# MCU_SLAVE.net
KiCad netlist of a schematic drawn in Altium Designer
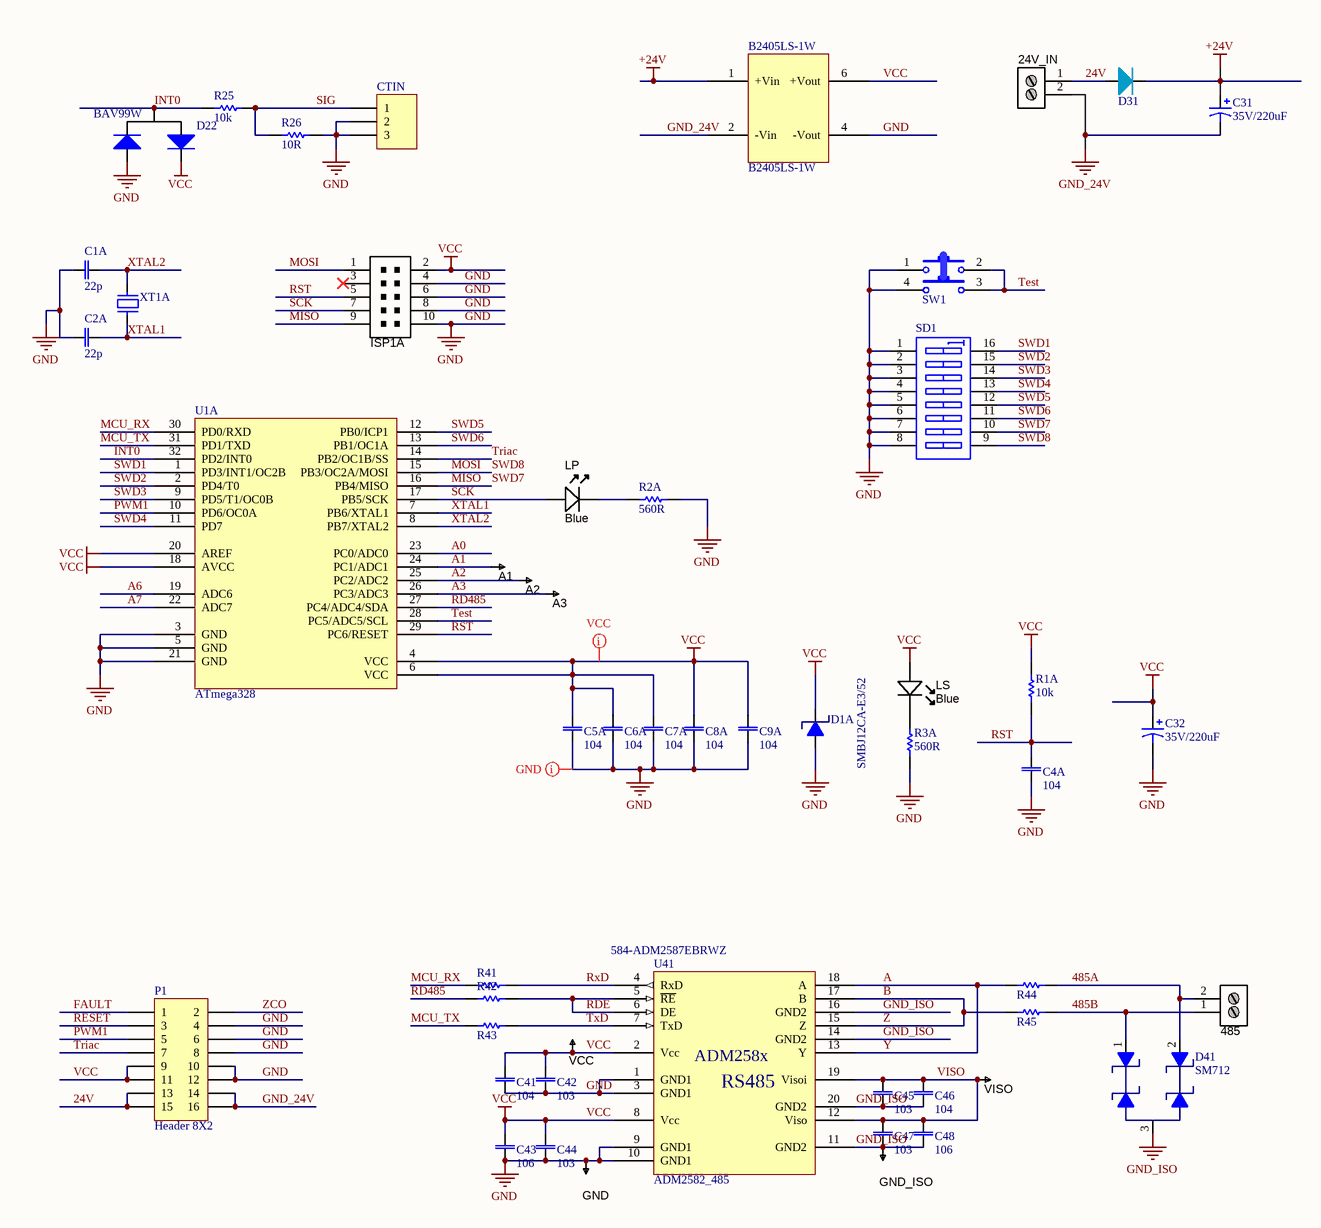
[diagram p0: MCU_SLAVE.SchDoc]

(export (version "E")
  (design (tool "Eeschema 10.0.6"))
  (components
    (comp (ref "24V_IN")
      (value "Giắc xanh 5.08mm")
      (footprint "2P_PCB1")
      (description "Terminal Block Screw Type THT 2-Position 3.81mm pitch")
      (libsource (lib "PBL - Connectors") (part "2P_ScrewTerm_90S_3.81MM"))
    )
    (comp (ref "485")
      (value "Giắc xanh 5.08mm")
      (footprint "2P_PCB1")
      (description "Terminal Block Screw Type THT 2-Position 3.81mm pitch")
      (libsource (lib "") (part "2P_ScrewTerm_90S_3.81MM_1"))
    )
    (comp (ref "A1")
      (value "TESTPOINT")
      (footprint "TP-R60")
      (description "SMD test pin")
      (libsource (lib "PBL - Test Points") (part "TESTPOINT"))
    )
    (comp (ref "A2")
      (value "TESTPOINT")
      (footprint "TP-R60")
      (description "SMD test pin")
      (libsource (lib "PBL - Test Points") (part "TESTPOINT"))
    )
    (comp (ref "A3")
      (value "TESTPOINT")
      (footprint "TP-R60")
      (description "SMD test pin")
      (libsource (lib "PBL - Test Points") (part "TESTPOINT"))
    )
    (comp (ref "B2405LS-1W")
      (value "B2405LS-1W")
      (footprint "Mornsun 1W")
      (libsource (lib "Tuan") (part "Mornsun 0505 1W"))
    )
    (comp (ref "C1A")
      (value "22p")
      (footprint "PBL - SMD Packages:CAPC2012N_F")
      (description "Capacitor non polarized")
      (fields (field (name "Comment") "Tụ điện dán 060322p"))
      (libsource (lib "Tuan") (part "CAP NP"))
    )
    (comp (ref "C2A")
      (value "22p")
      (footprint "PBL - SMD Packages:CAPC2012N_F")
      (description "Capacitor non polarized")
      (fields (field (name "Comment") "Tụ điện dán 060322p"))
      (libsource (lib "Tuan") (part "CAP NP"))
    )
    (comp (ref "C4A")
      (value "104")
      (footprint "PBL - SMD Packages:CAPC2012N_F")
      (description "Capacitor non polarized")
      (fields (field (name "Comment") "Tụ điện dán 0603104"))
      (libsource (lib "Tuan") (part "CAP NP"))
    )
    (comp (ref "C5A")
      (value "104")
      (footprint "PBL - SMD Packages:CAPC2012N_F")
      (description "Capacitor non polarized")
      (fields (field (name "Comment") "Tụ điện dán 0805104"))
      (libsource (lib "Tuan") (part "CAP NP"))
    )
    (comp (ref "C6A")
      (value "104")
      (footprint "PBL - SMD Packages:CAPC2012N_F")
      (description "Capacitor non polarized")
      (fields (field (name "Comment") "Tụ điện dán 0805104"))
      (libsource (lib "Tuan") (part "CAP NP"))
    )
    (comp (ref "C7A")
      (value "104")
      (footprint "PBL - SMD Packages:CAPC2012N_F")
      (description "Capacitor non polarized")
      (fields (field (name "Comment") "Tụ điện dán 0603104"))
      (libsource (lib "Tuan") (part "CAP NP"))
    )
    (comp (ref "C8A")
      (value "104")
      (footprint "PBL - SMD Packages:CAPC2012N_F")
      (description "Capacitor non polarized")
      (fields (field (name "Comment") "Tụ điện dán 0603104"))
      (libsource (lib "Tuan") (part "CAP NP"))
    )
    (comp (ref "C9A")
      (value "104")
      (footprint "PBL - SMD Packages:CAPC2012N_F")
      (description "Capacitor non polarized")
      (fields (field (name "Comment") "Tụ điện dán 0603104"))
      (libsource (lib "Tuan") (part "CAP NP"))
    )
    (comp (ref "C31")
      (value "35V/220uF")
      (footprint "CAPE3.5-5.0MM_Rad_10x14mm")
      (fields (field (name "Comment") "Tụ nhôm cắm35V/220uF"))
      (libsource (lib "Tuan") (part "Cap"))
    )
    (comp (ref "C32")
      (value "35V/220uF")
      (footprint "CAPE3.5-5.0MM_Rad_10x14mm")
      (fields (field (name "Comment") "Tụ nhôm cắm35V/220uF"))
      (libsource (lib "Tuan") (part "Cap"))
    )
    (comp (ref "C41")
      (value "104")
      (footprint "PBL - SMD Packages:CAPC2012N_F")
      (description "Capacitor non polarized")
      (fields (field (name "Comment") "Tụ điện dán 0805104"))
      (libsource (lib "Tuan") (part "CAP NP"))
    )
    (comp (ref "C42")
      (value "103")
      (footprint "PBL - SMD Packages:CAPC2012N_F")
      (description "Capacitor non polarized")
      (fields (field (name "Comment") "Tụ điện dán 0805103"))
      (libsource (lib "Tuan") (part "CAP NP"))
    )
    (comp (ref "C43")
      (value "106")
      (footprint "PBL - SMD Packages:CAPC2012N_F")
      (description "Capacitor non polarized")
      (fields (field (name "Comment") "Tụ điện dán 0805106"))
      (libsource (lib "Tuan") (part "CAP NP"))
    )
    (comp (ref "C44")
      (value "103")
      (footprint "PBL - SMD Packages:CAPC2012N_F")
      (description "Capacitor non polarized")
      (fields (field (name "Comment") "Tụ điện dán 0805103"))
      (libsource (lib "Tuan") (part "CAP NP"))
    )
    (comp (ref "C45")
      (value "103")
      (footprint "PBL - SMD Packages:CAPC2012N_F")
      (description "Capacitor non polarized")
      (fields (field (name "Comment") "Tụ điện dán 0805103"))
      (libsource (lib "Tuan") (part "CAP NP"))
    )
    (comp (ref "C46")
      (value "104")
      (footprint "PBL - SMD Packages:CAPC2012N_F")
      (description "Capacitor non polarized")
      (fields (field (name "Comment") "Tụ điện dán 0805104"))
      (libsource (lib "Tuan") (part "CAP NP"))
    )
    (comp (ref "C47")
      (value "103")
      (footprint "PBL - SMD Packages:CAPC2012N_F")
      (description "Capacitor non polarized")
      (fields (field (name "Comment") "Tụ điện dán 0805103"))
      (libsource (lib "Tuan") (part "CAP NP"))
    )
    (comp (ref "C48")
      (value "106")
      (footprint "PBL - SMD Packages:CAPC2012N_F")
      (description "Capacitor non polarized")
      (fields (field (name "Comment") "Tụ điện dán 0805106"))
      (libsource (lib "Tuan") (part "CAP NP"))
    )
    (comp (ref "CTIN")
      (value "Header 3")
      (footprint "HDR1X3")
      (description "Header, 3-Pin")
      (fields (field (name "PUBLISHER") "Altium Limited"))
      (libsource (lib "Miscellaneous Connectors") (part "Header 3"))
    )
    (comp (ref "D1A")
      (value "Đi ốt dánSMBJ12CA-E3/52")
      (footprint "DO-214AC")
      (description "TVS Diodes - Transient Voltage Suppressors")
      (fields (field (name "VL2") "SMBJ12CA-E3/52"))
      (libsource (lib "Tuan") (part "TVS Diodes"))
    )
    (comp (ref "D22")
      (value "Đi ốt dánBAV99Wchân SOT-323")
      (footprint "SOT323")
      (description "Diode Array 1 Pair Series Connection Standard 70V 215mA (DC) Surface Mount SC-70, SOT-323")
      (fields (field (name "VL1") "BAV99W"))
      (libsource (lib "Tuan") (part "BAV99W"))
    )
    (comp (ref "D31")
      (value "Đi ốt cắm")
      (footprint "PBL - SMD Packages:DO-214AC")
      (libsource (lib "Tuan") (part "Diode"))
    )
    (comp (ref "D41") (value "SM712") (footprint "SOT23 TOP") (libsource (lib "Tuan") (part "SM712")))
    (comp (ref "GND")
      (value "TESTPOINT")
      (footprint "TP-R60")
      (description "SMD test pin")
      (libsource (lib "PBL - Test Points") (part "TESTPOINT"))
    )
    (comp (ref "GND_ISO")
      (value "TESTPOINT")
      (footprint "TP-R60")
      (description "SMD test pin")
      (libsource (lib "PBL - Test Points") (part "TESTPOINT"))
    )
    (comp (ref "ISP1A")
      (value "Giắc đôi 5x2 chân 2.54mm")
      (footprint "10P_PCB_HEADER_BRD_MNT")
      (description "Header THD 10 POS Double-row 2.54mm pitch")
      (libsource (lib "PBL - Connectors") (part "CONN_HEADER_2x5P_0.100in_Male"))
    )
    (comp (ref "LP")
      (value "Blue")
      (footprint "LED-0805-K")
      (description "LED 0805 SMD Blue 100mcd 470nm")
      (fields (field (name "COLOR") "Blue"))
      (libsource (lib "PBL - Light Sources") (part "LED_SMD_Blue_0805_100mcd"))
    )
    (comp (ref "LS")
      (value "Blue")
      (footprint "LED-0805-K")
      (description "LED 0805 SMD Blue 100mcd 470nm")
      (fields (field (name "COLOR") "Blue"))
      (libsource (lib "PBL - Light Sources") (part "LED_SMD_Blue_0805_100mcd"))
    )
    (comp (ref "P1")
      (value "Header 8X2")
      (footprint "HDR2X8")
      (description "Header, 8-Pin, Dual row")
      (fields (field (name "PUBLISHER") "Altium Limited"))
      (libsource (lib "Miscellaneous Connectors") (part "Header 8X2"))
    )
    (comp (ref "R1A")
      (value "10k")
      (footprint "PBL - SMD Packages:RESC2012N_F")
      (description "Resistor")
      (fields (field (name "Comment") "Điện trở dán 060310k"))
      (libsource (lib "Tuan") (part "Res"))
    )
    (comp (ref "R2A")
      (value "560R")
      (footprint "PBL - SMD Packages:RESC2012N_F")
      (description "Resistor")
      (fields (field (name "Comment") "Điện trở dán 0603560R"))
      (libsource (lib "Tuan") (part "Res"))
    )
    (comp (ref "R3A")
      (value "560R")
      (footprint "PBL - SMD Packages:RESC2012N_F")
      (description "Resistor")
      (fields (field (name "Comment") "Điện trở dán 0603560R"))
      (libsource (lib "Tuan") (part "Res"))
    )
    (comp (ref "R25")
      (value "10k")
      (footprint "PBL - SMD Packages:RESC3216N")
      (description "Resistor")
      (fields (field (name "Comment") "Điện trở dán 120610k"))
      (libsource (lib "Tuan") (part "Res"))
    )
    (comp (ref "R26")
      (value "10R")
      (footprint "PBL - SMD Packages:RESC3216N")
      (description "Resistor")
      (fields (field (name "Comment") "Điện trở dán 120610R"))
      (libsource (lib "Tuan") (part "Res"))
    )
    (comp (ref "R41")
      (value "Điện trở dán 08050R")
      (footprint "PBL - SMD Packages:RESC2012N_F")
      (description "Resistor")
      (libsource (lib "Tuan") (part "Res"))
    )
    (comp (ref "R42")
      (value "Điện trở dán 08050R")
      (footprint "PBL - SMD Packages:RESC2012N_F")
      (description "Resistor")
      (libsource (lib "Tuan") (part "Res"))
    )
    (comp (ref "R43")
      (value "Điện trở dán 08050R")
      (footprint "PBL - SMD Packages:RESC2012N_F")
      (description "Resistor")
      (libsource (lib "Tuan") (part "Res"))
    )
    (comp (ref "R44")
      (value "Điện trở dán 08050R")
      (footprint "PBL - SMD Packages:RESC2012N_F")
      (description "Resistor")
      (libsource (lib "Tuan") (part "Res"))
    )
    (comp (ref "R45")
      (value "Điện trở dán 08050R")
      (footprint "PBL - SMD Packages:RESC2012N_F")
      (description "Resistor")
      (libsource (lib "Tuan") (part "Res"))
    )
    (comp (ref "SD1")
      (value "Công tắc gạt 8 kênh, 16 chân cắm DIP16")
      (footprint "DIP16/W0.3K")
      (description "DIP Switch, 8 Position, SPST")
      (libsource (lib "heromap") (part "SWDIP-8"))
    )
    (comp (ref "SW1")
      (value "Nút bấm 4 chân cắm12x12x6mm")
      (footprint "SW")
      (libsource (lib "Tuan") (part "SW-4P-Small"))
    )
    (comp (ref "U1A")
      (value "ATmega328")
      (footprint "TQFP32")
      (description "AVR AVR® ATmega Microcontroller IC 8-Bit 20MHz 8KB (4K x 16) FLASH 32-TQFP (7x7)")
      (libsource (lib "Tuan") (part "ATmega48/168/328"))
    )
    (comp (ref "U41")
      (value "ADM2582_485")
      (footprint "syhaunguyen:SO-20B")
      (description "ANALOG DEVICES   ADM2587EBRWZ   RS485 Transceiver, 3V-5.5V Supply, SOIC-20")
      (fields
        (field (name "SUPPLIER PART NUMBER 1") "584-ADM2587EBRWZ")
        (field (name "MANUFACTURER") "Analog Devices")
        (field (name "MANUFACTURER PART NUMBER") "ADM2587EBRWZ")
      )
      (libsource (lib "Tuan") (part "ADM2582_485"))
    )
    (comp (ref "VCC")
      (value "TESTPOINT")
      (footprint "TP-R60")
      (description "SMD test pin")
      (libsource (lib "PBL - Test Points") (part "TESTPOINT"))
    )
    (comp (ref "VISO")
      (value "TESTPOINT")
      (footprint "TP-R60")
      (description "SMD test pin")
      (libsource (lib "PBL - Test Points") (part "TESTPOINT"))
    )
    (comp (ref "XT1A")
      (value "Thạch anh cắm 16MHz")
      (footprint "XT2")
      (libsource (lib "Tuan") (part "Crystal"))
    )
  )
  (nets
    (net (code "1") (name "+24V") (class "Default")
      (node (ref "B2405LS-1W") (pin "1") (pinfunction "+Vin_1") (pintype "passive"))
      (node (ref "C31") (pin "1") (pinfunction "1_1") (pintype "passive"))
      (node (ref "D31") (pin "K") (pinfunction "K_K") (pintype "passive"))
    )
    (net (code "2") (name "/24V") (class "Default")
      (node (ref "24V_IN") (pin "1") (pinfunction "1_1") (pintype "passive"))
      (node (ref "D31") (pin "A") (pinfunction "A_A") (pintype "passive"))
      (node (ref "P1") (pin "13") (pinfunction "13_13") (pintype "passive"))
      (node (ref "P1") (pin "15") (pinfunction "15_15") (pintype "passive"))
    )
    (net (code "3") (name "/485A") (class "Default")
      (node (ref "485") (pin "2") (pinfunction "2_2") (pintype "passive"))
      (node (ref "D41") (pin "2") (pinfunction "IO2_2") (pintype "passive"))
      (node (ref "R44") (pin "2") (pinfunction "2_2") (pintype "passive"))
    )
    (net (code "4") (name "/485B") (class "Default")
      (node (ref "485") (pin "1") (pinfunction "1_1") (pintype "passive"))
      (node (ref "D41") (pin "1") (pinfunction "IO1_1") (pintype "passive"))
      (node (ref "R45") (pin "2") (pinfunction "2_2") (pintype "passive"))
    )
    (net (code "5") (name "/A") (class "Default")
      (node (ref "R44") (pin "1") (pinfunction "1_1") (pintype "passive"))
      (node (ref "U41") (pin "13") (pinfunction "Y_13") (pintype "passive"))
      (node (ref "U41") (pin "18") (pinfunction "A_18") (pintype "passive"))
    )
    (net (code "6") (name "/A0") (class "Default")
      (node (ref "U1A") (pin "23") (pinfunction "PC0/ADC0_23") (pintype "passive"))
    )
    (net (code "7") (name "/A1") (class "Default")
      (node (ref "A1") (pin "1") (pintype "passive"))
      (node (ref "U1A") (pin "24") (pinfunction "PC1/ADC1_24") (pintype "passive"))
    )
    (net (code "8") (name "/A2") (class "Default")
      (node (ref "A2") (pin "1") (pintype "passive"))
      (node (ref "U1A") (pin "25") (pinfunction "PC2/ADC2_25") (pintype "passive"))
    )
    (net (code "9") (name "/A3") (class "Default")
      (node (ref "A3") (pin "1") (pintype "passive"))
      (node (ref "U1A") (pin "26") (pinfunction "PC3/ADC3_26") (pintype "passive"))
    )
    (net (code "10") (name "/A6") (class "Default")
      (node (ref "U1A") (pin "19") (pinfunction "ADC6_19") (pintype "passive"))
    )
    (net (code "11") (name "/A7") (class "Default")
      (node (ref "U1A") (pin "22") (pinfunction "ADC7_22") (pintype "passive"))
    )
    (net (code "12") (name "/B") (class "Default")
      (node (ref "R45") (pin "1") (pinfunction "1_1") (pintype "passive"))
      (node (ref "U41") (pin "15") (pinfunction "Z_15") (pintype "passive"))
      (node (ref "U41") (pin "17") (pinfunction "B_17") (pintype "passive"))
    )
    (net (code "13") (name "/FAULT") (class "Default")
      (node (ref "P1") (pin "1") (pinfunction "1_1") (pintype "passive"))
    )
    (net (code "14") (name "/INT0") (class "Default")
      (node (ref "D22") (pin "3") (pinfunction "AK_3") (pintype "passive"))
      (node (ref "R25") (pin "2") (pinfunction "2_2") (pintype "passive"))
      (node (ref "U1A") (pin "32") (pinfunction "PD2/INT0_32") (pintype "passive"))
    )
    (net (code "15") (name "/MCU_RX") (class "Default")
      (node (ref "R41") (pin "1") (pinfunction "1_1") (pintype "passive"))
      (node (ref "U1A") (pin "30") (pinfunction "PD0/RXD_30") (pintype "passive"))
    )
    (net (code "16") (name "/MCU_TX") (class "Default")
      (node (ref "R43") (pin "1") (pinfunction "1_1") (pintype "passive"))
      (node (ref "U1A") (pin "31") (pinfunction "PD1/TXD_31") (pintype "passive"))
    )
    (net (code "17") (name "/MISO") (class "Default")
      (node (ref "ISP1A") (pin "9") (pinfunction "9_9") (pintype "passive"))
      (node (ref "SD1") (pin "10") (pinfunction "B7_10") (pintype "passive"))
      (node (ref "U1A") (pin "16") (pinfunction "PB4/MISO_16") (pintype "passive"))
    )
    (net (code "18") (name "/MOSI") (class "Default")
      (node (ref "ISP1A") (pin "1") (pinfunction "1_1") (pintype "passive"))
      (node (ref "SD1") (pin "9") (pinfunction "B8_9") (pintype "passive"))
      (node (ref "U1A") (pin "15") (pinfunction "PB3/OC2A/MOSI_15") (pintype "passive"))
    )
    (net (code "19") (name "/PWM1") (class "Default")
      (node (ref "P1") (pin "5") (pinfunction "5_5") (pintype "passive"))
      (node (ref "U1A") (pin "10") (pinfunction "PD6/OC0A_10") (pintype "passive"))
    )
    (net (code "20") (name "/RD485") (class "Default")
      (node (ref "R42") (pin "1") (pinfunction "1_1") (pintype "passive"))
      (node (ref "U1A") (pin "27") (pinfunction "PC4/ADC4/SDA_27") (pintype "passive"))
    )
    (net (code "21") (name "/RDE") (class "Default")
      (node (ref "R42") (pin "2") (pinfunction "2_2") (pintype "passive"))
      (node (ref "U41") (pin "5") (pinfunction "~{RE}_5") (pintype "input"))
      (node (ref "U41") (pin "6") (pinfunction "DE_6") (pintype "input"))
    )
    (net (code "22") (name "/RESET") (class "Default")
      (node (ref "P1") (pin "3") (pinfunction "3_3") (pintype "passive"))
    )
    (net (code "23") (name "/RST") (class "Default")
      (node (ref "C4A") (pin "2") (pinfunction "2_2") (pintype "passive"))
      (node (ref "ISP1A") (pin "5") (pinfunction "5_5") (pintype "passive"))
      (node (ref "R1A") (pin "1") (pinfunction "1_1") (pintype "passive"))
      (node (ref "U1A") (pin "29") (pinfunction "PC6/RESET_29") (pintype "passive"))
    )
    (net (code "24") (name "/RxD") (class "Default")
      (node (ref "R41") (pin "2") (pinfunction "2_2") (pintype "passive"))
      (node (ref "U41") (pin "4") (pinfunction "RxD_4") (pintype "output"))
    )
    (net (code "25") (name "/SCK") (class "Default")
      (node (ref "ISP1A") (pin "7") (pinfunction "7_7") (pintype "passive"))
      (node (ref "LP") (pin "A") (pinfunction "A_A") (pintype "passive"))
      (node (ref "U1A") (pin "17") (pinfunction "PB5/SCK_17") (pintype "passive"))
    )
    (net (code "26") (name "/SIG") (class "Default")
      (node (ref "CTIN") (pin "1") (pinfunction "1_1") (pintype "passive"))
      (node (ref "R25") (pin "1") (pinfunction "1_1") (pintype "passive"))
      (node (ref "R26") (pin "2") (pinfunction "2_2") (pintype "passive"))
    )
    (net (code "27") (name "/SWD1") (class "Default")
      (node (ref "SD1") (pin "16") (pinfunction "B1_16") (pintype "passive"))
      (node (ref "U1A") (pin "1") (pinfunction "PD3/INT1/OC2B_1") (pintype "passive"))
    )
    (net (code "28") (name "/SWD2") (class "Default")
      (node (ref "SD1") (pin "15") (pinfunction "B2_15") (pintype "passive"))
      (node (ref "U1A") (pin "2") (pinfunction "PD4/T0_2") (pintype "passive"))
    )
    (net (code "29") (name "/SWD3") (class "Default")
      (node (ref "SD1") (pin "14") (pinfunction "B3_14") (pintype "passive"))
      (node (ref "U1A") (pin "9") (pinfunction "PD5/T1/OC0B_9") (pintype "passive"))
    )
    (net (code "30") (name "/SWD4") (class "Default")
      (node (ref "SD1") (pin "13") (pinfunction "B4_13") (pintype "passive"))
      (node (ref "U1A") (pin "11") (pinfunction "PD7_11") (pintype "passive"))
    )
    (net (code "31") (name "/SWD5") (class "Default")
      (node (ref "SD1") (pin "12") (pinfunction "B5_12") (pintype "passive"))
      (node (ref "U1A") (pin "12") (pinfunction "PB0/ICP1_12") (pintype "passive"))
    )
    (net (code "32") (name "/SWD6") (class "Default")
      (node (ref "SD1") (pin "11") (pinfunction "B6_11") (pintype "passive"))
      (node (ref "U1A") (pin "13") (pinfunction "PB1/OC1A_13") (pintype "passive"))
    )
    (net (code "33") (name "/Test") (class "Default")
      (node (ref "SW1") (pin "2") (pinfunction "2_2") (pintype "passive"))
      (node (ref "SW1") (pin "3") (pinfunction "3_3") (pintype "passive"))
      (node (ref "U1A") (pin "28") (pinfunction "PC5/ADC5/SCL_28") (pintype "passive"))
    )
    (net (code "34") (name "/Triac") (class "Default")
      (node (ref "P1") (pin "7") (pinfunction "7_7") (pintype "passive"))
      (node (ref "U1A") (pin "14") (pinfunction "PB2/OC1B/SS_14") (pintype "passive"))
    )
    (net (code "35") (name "/TxD") (class "Default")
      (node (ref "R43") (pin "2") (pinfunction "2_2") (pintype "passive"))
      (node (ref "U41") (pin "7") (pinfunction "TxD_7") (pintype "input"))
    )
    (net (code "36") (name "/VISO") (class "Default")
      (node (ref "C45") (pin "2") (pinfunction "2_2") (pintype "passive"))
      (node (ref "C46") (pin "2") (pinfunction "2_2") (pintype "passive"))
      (node (ref "C47") (pin "2") (pinfunction "2_2") (pintype "passive"))
      (node (ref "C48") (pin "2") (pinfunction "2_2") (pintype "passive"))
      (node (ref "U41") (pin "12") (pinfunction "Viso_12") (pintype "power_in"))
      (node (ref "U41") (pin "19") (pinfunction "Visoi_19") (pintype "power_in"))
      (node (ref "VISO") (pin "1") (pintype "passive"))
    )
    (net (code "37") (name "/XTAL1") (class "Default")
      (node (ref "C2A") (pin "1") (pinfunction "1_1") (pintype "passive"))
      (node (ref "U1A") (pin "7") (pinfunction "PB6/XTAL1_7") (pintype "passive"))
      (node (ref "XT1A") (pin "1") (pinfunction "1_1") (pintype "passive"))
    )
    (net (code "38") (name "/XTAL2") (class "Default")
      (node (ref "C1A") (pin "1") (pinfunction "1_1") (pintype "passive"))
      (node (ref "U1A") (pin "8") (pinfunction "PB7/XTAL2_8") (pintype "passive"))
      (node (ref "XT1A") (pin "2") (pinfunction "2_2") (pintype "passive"))
    )
    (net (code "39") (name "/ZCO") (class "Default")
      (node (ref "P1") (pin "2") (pinfunction "2_2") (pintype "passive"))
    )
    (net (code "40") (name "GND") (class "Default")
      (node (ref "B2405LS-1W") (pin "4") (pinfunction "-Vout_4") (pintype "passive"))
      (node (ref "C1A") (pin "2") (pinfunction "2_2") (pintype "passive"))
      (node (ref "C2A") (pin "2") (pinfunction "2_2") (pintype "passive"))
      (node (ref "C32") (pin "2") (pinfunction "2_2") (pintype "passive"))
      (node (ref "C41") (pin "1") (pinfunction "1_1") (pintype "passive"))
      (node (ref "C42") (pin "1") (pinfunction "1_1") (pintype "passive"))
      (node (ref "C43") (pin "1") (pinfunction "1_1") (pintype "passive"))
      (node (ref "C44") (pin "1") (pinfunction "1_1") (pintype "passive"))
      (node (ref "C4A") (pin "1") (pinfunction "1_1") (pintype "passive"))
      (node (ref "C5A") (pin "1") (pinfunction "1_1") (pintype "passive"))
      (node (ref "C6A") (pin "1") (pinfunction "1_1") (pintype "passive"))
      (node (ref "C7A") (pin "1") (pinfunction "1_1") (pintype "passive"))
      (node (ref "C8A") (pin "1") (pinfunction "1_1") (pintype "passive"))
      (node (ref "C9A") (pin "1") (pinfunction "1_1") (pintype "passive"))
      (node (ref "CTIN") (pin "2") (pinfunction "2_2") (pintype "passive"))
      (node (ref "CTIN") (pin "3") (pinfunction "3_3") (pintype "passive"))
      (node (ref "D1A") (pin "A") (pinfunction "A_A") (pintype "passive"))
      (node (ref "D22") (pin "1") (pinfunction "A_1") (pintype "passive"))
      (node (ref "GND") (pin "1") (pintype "passive"))
      (node (ref "ISP1A") (pin "10") (pinfunction "10_10") (pintype "passive"))
      (node (ref "ISP1A") (pin "4") (pinfunction "4_4") (pintype "passive"))
      (node (ref "ISP1A") (pin "6") (pinfunction "6_6") (pintype "passive"))
      (node (ref "ISP1A") (pin "8") (pinfunction "8_8") (pintype "passive"))
      (node (ref "P1") (pin "10") (pinfunction "10_10") (pintype "passive"))
      (node (ref "P1") (pin "12") (pinfunction "12_12") (pintype "passive"))
      (node (ref "P1") (pin "4") (pinfunction "4_4") (pintype "passive"))
      (node (ref "P1") (pin "6") (pinfunction "6_6") (pintype "passive"))
      (node (ref "P1") (pin "8") (pinfunction "8_8") (pintype "passive"))
      (node (ref "R26") (pin "1") (pinfunction "1_1") (pintype "passive"))
      (node (ref "R2A") (pin "2") (pinfunction "2_2") (pintype "passive"))
      (node (ref "R3A") (pin "1") (pinfunction "1_1") (pintype "passive"))
      (node (ref "SD1") (pin "1") (pinfunction "A1_1") (pintype "passive"))
      (node (ref "SD1") (pin "2") (pinfunction "A2_2") (pintype "passive"))
      (node (ref "SD1") (pin "3") (pinfunction "A3_3") (pintype "passive"))
      (node (ref "SD1") (pin "4") (pinfunction "A4_4") (pintype "passive"))
      (node (ref "SD1") (pin "5") (pinfunction "A5_5") (pintype "passive"))
      (node (ref "SD1") (pin "6") (pinfunction "A6_6") (pintype "passive"))
      (node (ref "SD1") (pin "7") (pinfunction "A7_7") (pintype "passive"))
      (node (ref "SD1") (pin "8") (pinfunction "A8_8") (pintype "passive"))
      (node (ref "SW1") (pin "1") (pinfunction "1_1") (pintype "passive"))
      (node (ref "SW1") (pin "4") (pinfunction "4_4") (pintype "passive"))
      (node (ref "U1A") (pin "21") (pinfunction "GND_21") (pintype "power_in"))
      (node (ref "U1A") (pin "3") (pinfunction "GND_3") (pintype "power_in"))
      (node (ref "U1A") (pin "5") (pinfunction "GND_5") (pintype "power_in"))
      (node (ref "U41") (pin "1") (pinfunction "GND1_1") (pintype "power_in"))
      (node (ref "U41") (pin "10") (pinfunction "GND1_10") (pintype "power_in"))
      (node (ref "U41") (pin "3") (pinfunction "GND1_3") (pintype "power_in"))
      (node (ref "U41") (pin "9") (pinfunction "GND1_9") (pintype "power_in"))
    )
    (net (code "41") (name "GND_24V") (class "Default")
      (node (ref "24V_IN") (pin "2") (pinfunction "2_2") (pintype "passive"))
      (node (ref "B2405LS-1W") (pin "2") (pinfunction "-Vin_2") (pintype "passive"))
      (node (ref "C31") (pin "2") (pinfunction "2_2") (pintype "passive"))
      (node (ref "P1") (pin "14") (pinfunction "14_14") (pintype "passive"))
      (node (ref "P1") (pin "16") (pinfunction "16_16") (pintype "passive"))
    )
    (net (code "42") (name "GND_ISO") (class "Default")
      (node (ref "C45") (pin "1") (pinfunction "1_1") (pintype "passive"))
      (node (ref "C46") (pin "1") (pinfunction "1_1") (pintype "passive"))
      (node (ref "C47") (pin "1") (pinfunction "1_1") (pintype "passive"))
      (node (ref "C48") (pin "1") (pinfunction "1_1") (pintype "passive"))
      (node (ref "D41") (pin "3") (pinfunction "GND_3") (pintype "passive"))
      (node (ref "GND_ISO") (pin "1") (pintype "passive"))
      (node (ref "U41") (pin "11") (pinfunction "GND2_11") (pintype "power_in"))
      (node (ref "U41") (pin "14") (pinfunction "GND2_14") (pintype "power_in"))
      (node (ref "U41") (pin "16") (pinfunction "GND2_16") (pintype "power_in"))
      (node (ref "U41") (pin "20") (pinfunction "GND2_20") (pintype "power_in"))
    )
    (net (code "43") (name "Net-(LP-PadK)") (class "Default")
      (node (ref "LP") (pin "K") (pinfunction "K_K") (pintype "passive"))
      (node (ref "R2A") (pin "1") (pinfunction "1_1") (pintype "passive"))
    )
    (net (code "44") (name "Net-(LS-PadK)") (class "Default")
      (node (ref "LS") (pin "K") (pinfunction "K_K") (pintype "passive"))
      (node (ref "R3A") (pin "2") (pinfunction "2_2") (pintype "passive"))
    )
    (net (code "45") (name "VCC") (class "Default")
      (node (ref "B2405LS-1W") (pin "6") (pinfunction "+Vout_6") (pintype "passive"))
      (node (ref "C32") (pin "1") (pinfunction "1_1") (pintype "passive"))
      (node (ref "C41") (pin "2") (pinfunction "2_2") (pintype "passive"))
      (node (ref "C42") (pin "2") (pinfunction "2_2") (pintype "passive"))
      (node (ref "C43") (pin "2") (pinfunction "2_2") (pintype "passive"))
      (node (ref "C44") (pin "2") (pinfunction "2_2") (pintype "passive"))
      (node (ref "C5A") (pin "2") (pinfunction "2_2") (pintype "passive"))
      (node (ref "C6A") (pin "2") (pinfunction "2_2") (pintype "passive"))
      (node (ref "C7A") (pin "2") (pinfunction "2_2") (pintype "passive"))
      (node (ref "C8A") (pin "2") (pinfunction "2_2") (pintype "passive"))
      (node (ref "C9A") (pin "2") (pinfunction "2_2") (pintype "passive"))
      (node (ref "D1A") (pin "K") (pinfunction "K_K") (pintype "passive"))
      (node (ref "D22") (pin "2") (pinfunction "K_2") (pintype "passive"))
      (node (ref "ISP1A") (pin "2") (pinfunction "2_2") (pintype "passive"))
      (node (ref "LS") (pin "A") (pinfunction "A_A") (pintype "passive"))
      (node (ref "P1") (pin "11") (pinfunction "11_11") (pintype "passive"))
      (node (ref "P1") (pin "9") (pinfunction "9_9") (pintype "passive"))
      (node (ref "R1A") (pin "2") (pinfunction "2_2") (pintype "passive"))
      (node (ref "U1A") (pin "18") (pinfunction "AVCC_18") (pintype "passive"))
      (node (ref "U1A") (pin "20") (pinfunction "AREF_20") (pintype "passive"))
      (node (ref "U1A") (pin "4") (pinfunction "VCC_4") (pintype "passive"))
      (node (ref "U1A") (pin "6") (pinfunction "VCC_6") (pintype "passive"))
      (node (ref "U41") (pin "2") (pinfunction "Vcc_2") (pintype "power_in"))
      (node (ref "U41") (pin "8") (pinfunction "Vcc_8") (pintype "power_in"))
      (node (ref "VCC") (pin "1") (pintype "passive"))
    )
    (net (code "46") (name "unconnected-(ISP1A-Pad3)") (class "Default")
      (node (ref "ISP1A") (pin "3") (pinfunction "3_3") (pintype "passive+no_connect"))
    )
  )
)
